# ERN_Main.net
KiCad netlist of a schematic drawn in Altium Designer
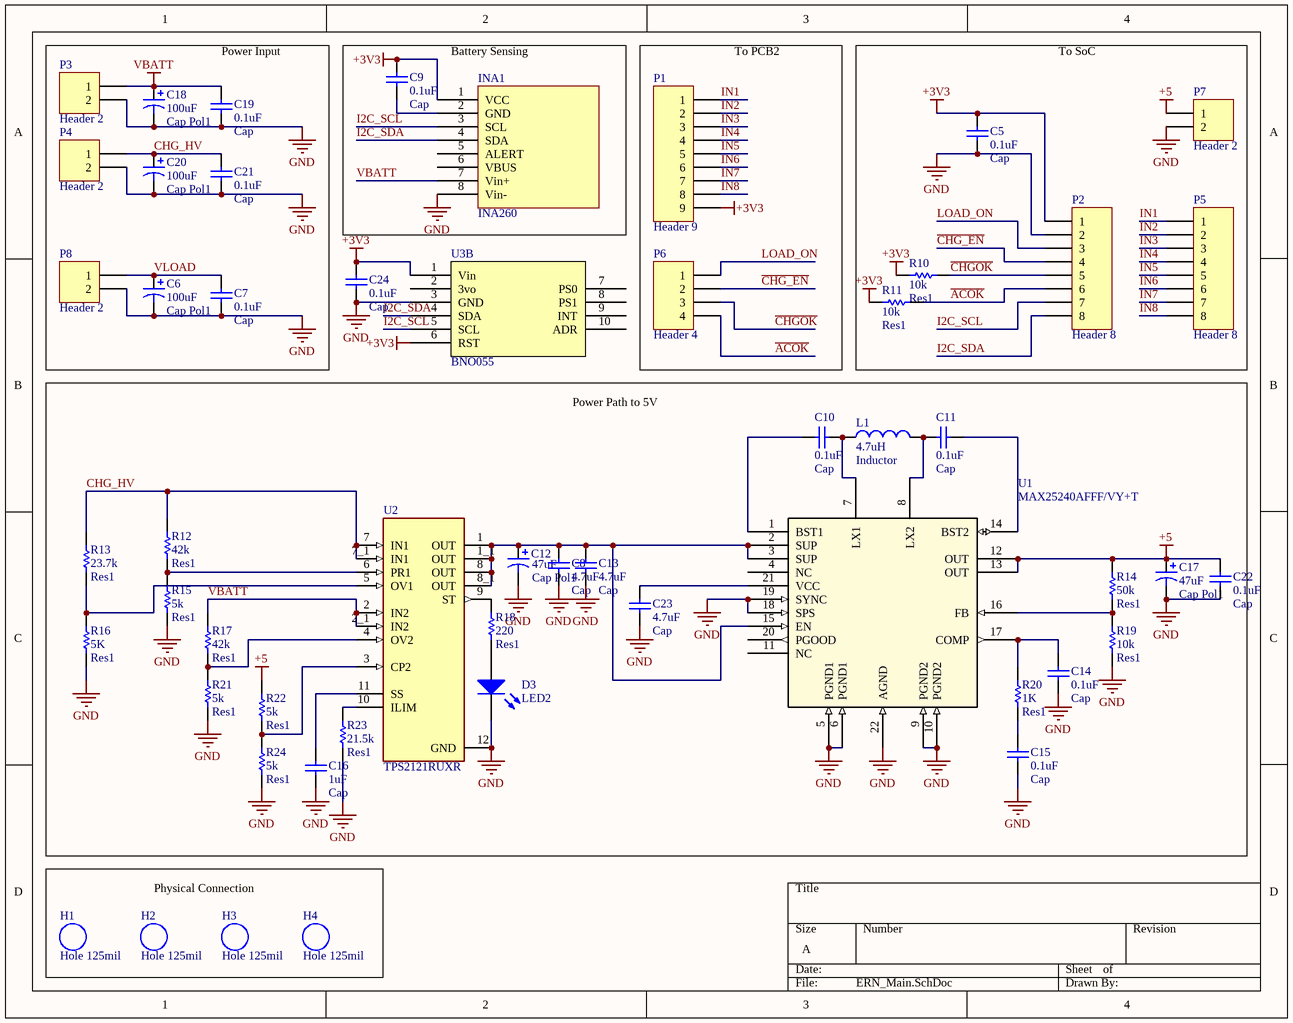
[diagram p0: ERN_Main.SchDoc]

(export (version "E")
  (design (tool "Eeschema 10.0.6"))
  (components
    (comp (ref "C5")
      (value "Cap")
      (footprint "RAD-0.3")
      (description "Capacitor")
      (fields (field (name "ALTIUM_VALUE") "0.1uF") (field (name "PUBLISHER") "Altium Limited"))
      (libsource (lib "Miscellaneous Devices") (part "Cap"))
    )
    (comp (ref "C6")
      (value "Cap Pol1")
      (footprint "Cap_47uF_100uF")
      (description "Polarized Capacitor (Radial)")
      (fields (field (name "ALTIUM_VALUE") "100uF") (field (name "PUBLISHER") "Altium Limited"))
      (libsource (lib "Miscellaneous Devices") (part "Cap Pol1"))
    )
    (comp (ref "C7")
      (value "Cap")
      (footprint "RAD-0.3")
      (description "Capacitor")
      (fields (field (name "ALTIUM_VALUE") "0.1uF") (field (name "PUBLISHER") "Altium Limited"))
      (libsource (lib "Miscellaneous Devices") (part "Cap"))
    )
    (comp (ref "C8")
      (value "Cap")
      (footprint "c0805")
      (description "Capacitor")
      (fields (field (name "ALTIUM_VALUE") "4.7uF") (field (name "PUBLISHER") "Altium Limited"))
      (libsource (lib "Miscellaneous Devices") (part "Cap"))
    )
    (comp (ref "C9")
      (value "Cap")
      (footprint "RAD-0.3")
      (description "Capacitor")
      (fields (field (name "ALTIUM_VALUE") "0.1uF") (field (name "PUBLISHER") "Altium Limited"))
      (libsource (lib "Miscellaneous Devices") (part "Cap"))
    )
    (comp (ref "C10")
      (value "Cap")
      (footprint "c0805")
      (description "Capacitor")
      (fields (field (name "ALTIUM_VALUE") "0.1uF") (field (name "PUBLISHER") "Altium Limited"))
      (libsource (lib "Miscellaneous Devices") (part "Cap"))
    )
    (comp (ref "C11")
      (value "Cap")
      (footprint "c0805")
      (description "Capacitor")
      (fields (field (name "ALTIUM_VALUE") "0.1uF") (field (name "PUBLISHER") "Altium Limited"))
      (libsource (lib "Miscellaneous Devices") (part "Cap"))
    )
    (comp (ref "C12")
      (value "Cap Pol1")
      (footprint "Cap_47uF_100uF")
      (description "Polarized Capacitor (Radial)")
      (fields (field (name "ALTIUM_VALUE") "47uF") (field (name "PUBLISHER") "Altium Limited"))
      (libsource (lib "Miscellaneous Devices") (part "Cap Pol1"))
    )
    (comp (ref "C13")
      (value "Cap")
      (footprint "c0805")
      (description "Capacitor")
      (fields (field (name "ALTIUM_VALUE") "4.7uF") (field (name "PUBLISHER") "Altium Limited"))
      (libsource (lib "Miscellaneous Devices") (part "Cap"))
    )
    (comp (ref "C14")
      (value "Cap")
      (footprint "RAD-0.3")
      (description "Capacitor")
      (fields (field (name "ALTIUM_VALUE") "0.1uF") (field (name "PUBLISHER") "Altium Limited"))
      (libsource (lib "Miscellaneous Devices") (part "Cap"))
    )
    (comp (ref "C15")
      (value "Cap")
      (footprint "RAD-0.3")
      (description "Capacitor")
      (fields (field (name "ALTIUM_VALUE") "0.1uF") (field (name "PUBLISHER") "Altium Limited"))
      (libsource (lib "Miscellaneous Devices") (part "Cap"))
    )
    (comp (ref "C16")
      (value "Cap")
      (footprint "C0805")
      (description "Capacitor")
      (fields (field (name "ALTIUM_VALUE") "1uF") (field (name "PUBLISHER") "Altium Limited"))
      (libsource (lib "Miscellaneous Devices") (part "Cap"))
    )
    (comp (ref "C17")
      (value "Cap Pol1")
      (footprint "Cap_47uF_100uF")
      (description "Polarized Capacitor (Radial)")
      (fields (field (name "ALTIUM_VALUE") "47uF") (field (name "PUBLISHER") "Altium Limited"))
      (libsource (lib "Miscellaneous Devices") (part "Cap Pol1"))
    )
    (comp (ref "C18")
      (value "Cap Pol1")
      (footprint "Cap_47uF_100uF")
      (description "Polarized Capacitor (Radial)")
      (fields (field (name "ALTIUM_VALUE") "100uF") (field (name "PUBLISHER") "Altium Limited"))
      (libsource (lib "Miscellaneous Devices") (part "Cap Pol1"))
    )
    (comp (ref "C19")
      (value "Cap")
      (footprint "RAD-0.3")
      (description "Capacitor")
      (fields (field (name "ALTIUM_VALUE") "0.1uF") (field (name "PUBLISHER") "Altium Limited"))
      (libsource (lib "Miscellaneous Devices") (part "Cap"))
    )
    (comp (ref "C20")
      (value "Cap Pol1")
      (footprint "Cap_47uF_100uF")
      (description "Polarized Capacitor (Radial)")
      (fields (field (name "ALTIUM_VALUE") "100uF") (field (name "PUBLISHER") "Altium Limited"))
      (libsource (lib "Miscellaneous Devices") (part "Cap Pol1"))
    )
    (comp (ref "C21")
      (value "Cap")
      (footprint "RAD-0.3")
      (description "Capacitor")
      (fields (field (name "ALTIUM_VALUE") "0.1uF") (field (name "PUBLISHER") "Altium Limited"))
      (libsource (lib "Miscellaneous Devices") (part "Cap"))
    )
    (comp (ref "C22")
      (value "Cap")
      (footprint "RAD-0.3")
      (description "Capacitor")
      (fields (field (name "ALTIUM_VALUE") "0.1uF") (field (name "PUBLISHER") "Altium Limited"))
      (libsource (lib "Miscellaneous Devices") (part "Cap"))
    )
    (comp (ref "C23")
      (value "Cap")
      (footprint "c0805")
      (description "Capacitor")
      (fields (field (name "ALTIUM_VALUE") "4.7uF") (field (name "PUBLISHER") "Altium Limited"))
      (libsource (lib "Miscellaneous Devices") (part "Cap"))
    )
    (comp (ref "C24")
      (value "Cap")
      (footprint "RAD-0.3")
      (description "Capacitor")
      (fields (field (name "ALTIUM_VALUE") "0.1uF") (field (name "PUBLISHER") "Altium Limited"))
      (libsource (lib "Miscellaneous Devices") (part "Cap"))
    )
    (comp (ref "D3")
      (value "LED2")
      (footprint "led-0")
      (description "Typical RED, GREEN, YELLOW, AMBER GaAs LED")
      (fields (field (name "PUBLISHER") "Altium Limited"))
      (libsource (lib "Miscellaneous Devices") (part "LED2"))
    )
    (comp (ref "H1")
      (value "Hole 125mil")
      (footprint "Hole 125mil")
      (libsource (lib "ECE Lib 22") (part "Hole 125mil"))
    )
    (comp (ref "H2")
      (value "Hole 125mil")
      (footprint "Hole 125mil")
      (libsource (lib "ECE Lib 22") (part "Hole 125mil"))
    )
    (comp (ref "H3")
      (value "Hole 125mil")
      (footprint "Hole 125mil")
      (libsource (lib "ECE Lib 22") (part "Hole 125mil"))
    )
    (comp (ref "H4")
      (value "Hole 125mil")
      (footprint "Hole 125mil")
      (libsource (lib "ECE Lib 22") (part "Hole 125mil"))
    )
    (comp (ref "INA1")
      (value "INA260")
      (footprint "INA260_Breakout")
      (description "Voltage and current sensor")
      (libsource (lib "ERN") (part "INA260_Breakout"))
    )
    (comp (ref "L1")
      (value "Inductor")
      (footprint "SRP6540-4R7M")
      (fields (field (name "ALTIUM_VALUE") "4.7uH") (field (name "PUBLISHER") "Altium Limited"))
      (libsource (lib "Miscellaneous Devices") (part "Inductor"))
    )
    (comp (ref "P1")
      (value "Header 9")
      (footprint "HDR1X9")
      (description "Header, 9-Pin")
      (fields (field (name "PUBLISHER") "Altium Limited"))
      (libsource (lib "Miscellaneous Connectors") (part "Header 9"))
    )
    (comp (ref "P2")
      (value "Header 8")
      (footprint "HDR1X8")
      (description "Header, 8-Pin")
      (fields (field (name "PUBLISHER") "Altium Limited"))
      (libsource (lib "Miscellaneous Connectors") (part "Header 8"))
    )
    (comp (ref "P3")
      (value "Header 2")
      (footprint "HDR1X2")
      (description "Header, 2-Pin")
      (fields (field (name "PUBLISHER") "Altium Limited"))
      (libsource (lib "Miscellaneous Connectors") (part "Header 2"))
    )
    (comp (ref "P4")
      (value "Header 2")
      (footprint "HDR1X2")
      (description "Header, 2-Pin")
      (fields (field (name "PUBLISHER") "Altium Limited"))
      (libsource (lib "Miscellaneous Connectors") (part "Header 2"))
    )
    (comp (ref "P5")
      (value "Header 8")
      (footprint "HDR1X8")
      (description "Header, 8-Pin")
      (fields (field (name "PUBLISHER") "Altium Limited"))
      (libsource (lib "Miscellaneous Connectors") (part "Header 8"))
    )
    (comp (ref "P6")
      (value "Header 4")
      (footprint "HDR1X4")
      (description "Header, 4-Pin")
      (fields (field (name "PUBLISHER") "Altium Limited"))
      (libsource (lib "Miscellaneous Connectors") (part "Header 4"))
    )
    (comp (ref "P7")
      (value "Header 2")
      (footprint "HDR1X2")
      (description "Header, 2-Pin")
      (fields (field (name "PUBLISHER") "Altium Limited"))
      (libsource (lib "") (part "Header 2_1"))
    )
    (comp (ref "P8")
      (value "Header 2")
      (footprint "HDR1X2")
      (description "Header, 2-Pin")
      (fields (field (name "PUBLISHER") "Altium Limited"))
      (libsource (lib "Miscellaneous Connectors") (part "Header 2"))
    )
    (comp (ref "R10")
      (value "Res1")
      (footprint "AXIAL-0.3")
      (description "Resistor")
      (fields (field (name "ALTIUM_VALUE") "10k") (field (name "PUBLISHER") "Altium Limited"))
      (libsource (lib "Miscellaneous Devices") (part "Res1"))
    )
    (comp (ref "R11")
      (value "Res1")
      (footprint "AXIAL-0.3")
      (description "Resistor")
      (fields (field (name "ALTIUM_VALUE") "10k") (field (name "PUBLISHER") "Altium Limited"))
      (libsource (lib "Miscellaneous Devices") (part "Res1"))
    )
    (comp (ref "R12")
      (value "Res1")
      (footprint "AXIAL-0.3")
      (description "Resistor")
      (fields (field (name "ALTIUM_VALUE") "42k") (field (name "PUBLISHER") "Altium Limited"))
      (libsource (lib "Miscellaneous Devices") (part "Res1"))
    )
    (comp (ref "R13")
      (value "Res1")
      (footprint "AXIAL-0.3")
      (description "Resistor")
      (fields (field (name "ALTIUM_VALUE") "23.7k") (field (name "PUBLISHER") "Altium Limited"))
      (libsource (lib "Miscellaneous Devices") (part "Res1"))
    )
    (comp (ref "R14")
      (value "Res1")
      (footprint "AXIAL-0.3")
      (description "Resistor")
      (fields (field (name "ALTIUM_VALUE") "50k") (field (name "PUBLISHER") "Altium Limited"))
      (libsource (lib "Miscellaneous Devices") (part "Res1"))
    )
    (comp (ref "R15")
      (value "Res1")
      (footprint "AXIAL-0.3")
      (description "Resistor")
      (fields (field (name "ALTIUM_VALUE") "5k") (field (name "PUBLISHER") "Altium Limited"))
      (libsource (lib "Miscellaneous Devices") (part "Res1"))
    )
    (comp (ref "R16")
      (value "Res1")
      (footprint "AXIAL-0.3")
      (description "Resistor")
      (fields (field (name "ALTIUM_VALUE") "5K") (field (name "PUBLISHER") "Altium Limited"))
      (libsource (lib "Miscellaneous Devices") (part "Res1"))
    )
    (comp (ref "R17")
      (value "Res1")
      (footprint "AXIAL-0.3")
      (description "Resistor")
      (fields (field (name "ALTIUM_VALUE") "42k") (field (name "PUBLISHER") "Altium Limited"))
      (libsource (lib "Miscellaneous Devices") (part "Res1"))
    )
    (comp (ref "R18")
      (value "Res1")
      (footprint "AXIAL-0.3")
      (description "Resistor")
      (fields (field (name "ALTIUM_VALUE") "220") (field (name "PUBLISHER") "Altium Limited"))
      (libsource (lib "Miscellaneous Devices") (part "Res1"))
    )
    (comp (ref "R19")
      (value "Res1")
      (footprint "AXIAL-0.3")
      (description "Resistor")
      (fields (field (name "ALTIUM_VALUE") "10k") (field (name "PUBLISHER") "Altium Limited"))
      (libsource (lib "Miscellaneous Devices") (part "Res1"))
    )
    (comp (ref "R20")
      (value "Res1")
      (footprint "AXIAL-0.3")
      (description "Resistor")
      (fields (field (name "ALTIUM_VALUE") "1K") (field (name "PUBLISHER") "Altium Limited"))
      (libsource (lib "Miscellaneous Devices") (part "Res1"))
    )
    (comp (ref "R21")
      (value "Res1")
      (footprint "AXIAL-0.3")
      (description "Resistor")
      (fields (field (name "ALTIUM_VALUE") "5k") (field (name "PUBLISHER") "Altium Limited"))
      (libsource (lib "Miscellaneous Devices") (part "Res1"))
    )
    (comp (ref "R22")
      (value "Res1")
      (footprint "AXIAL-0.3")
      (description "Resistor")
      (fields (field (name "ALTIUM_VALUE") "5k") (field (name "PUBLISHER") "Altium Limited"))
      (libsource (lib "Miscellaneous Devices") (part "Res1"))
    )
    (comp (ref "R23")
      (value "Res1")
      (footprint "AXIAL-0.3")
      (description "Resistor")
      (fields (field (name "ALTIUM_VALUE") "21.5k") (field (name "PUBLISHER") "Altium Limited"))
      (libsource (lib "Miscellaneous Devices") (part "Res1"))
    )
    (comp (ref "R24")
      (value "Res1")
      (footprint "AXIAL-0.3")
      (description "Resistor")
      (fields (field (name "ALTIUM_VALUE") "5k") (field (name "PUBLISHER") "Altium Limited"))
      (libsource (lib "Miscellaneous Devices") (part "Res1"))
    )
    (comp (ref "U1")
      (value "MAX25240AFFF/VY+T")
      (footprint "21-100399_90-100137_ADI - duplicate")
      (description "Automotive 2V to 36V, 6A Buck-Boost Converters")
      (fields (field (name "COPYRIGHT") "Copyright (C) 2025 Ultra Librarian. All rights reserved."))
      (libsource (lib "ERN") (part "MAX25240AFFFVY+T"))
    )
    (comp (ref "U2")
      (value "TPS2121RUXR")
      (footprint "IC_TPS2121RUXR")
      (description "2.7-V&nbsp;to 22-V, 56-mâ„¦, 4.5-A, power mux with seamless switchover")
      (fields (field (name "MF") "Texas Instruments"))
      (libsource (lib "ERN") (part "TPS2121RUXR"))
    )
    (comp (ref "U3")
      (value "BNO055")
      (footprint "BNO055_Breakout")
      (description "Adafruit IMU Breakout")
      (libsource (lib "ERN") (part "BNO055_Breakout"))
    )
  )
  (nets
    (net (code "1") (name "+3V3") (class "Default")
      (node (ref "C24") (pin "1") (pinfunction "1_1") (pintype "passive"))
      (node (ref "C5") (pin "2") (pinfunction "2_2") (pintype "passive"))
      (node (ref "C9") (pin "1") (pinfunction "1_1") (pintype "passive"))
      (node (ref "INA1") (pin "1") (pinfunction "VCC_1") (pintype "passive"))
      (node (ref "P1") (pin "9") (pinfunction "9_9") (pintype "passive"))
      (node (ref "P2") (pin "1") (pinfunction "1_1") (pintype "passive"))
      (node (ref "R10") (pin "1") (pinfunction "1_1") (pintype "passive"))
      (node (ref "R11") (pin "1") (pinfunction "1_1") (pintype "passive"))
      (node (ref "U3") (pin "1") (pinfunction "Vin_1") (pintype "passive"))
      (node (ref "U3") (pin "6") (pinfunction "RST_6") (pintype "passive"))
    )
    (net (code "2") (name "+5") (class "Default")
      (node (ref "C17") (pin "1") (pinfunction "1_1") (pintype "passive"))
      (node (ref "C22") (pin "2") (pinfunction "2_2") (pintype "passive"))
      (node (ref "P7") (pin "1") (pinfunction "1_1") (pintype "passive"))
      (node (ref "R14") (pin "1") (pinfunction "1_1") (pintype "passive"))
      (node (ref "R22") (pin "1") (pinfunction "1_1") (pintype "passive"))
      (node (ref "U1") (pin "12") (pinfunction "OUT_12") (pintype "power_in"))
      (node (ref "U1") (pin "13") (pinfunction "OUT_13") (pintype "power_in"))
    )
    (net (code "3") (name "/CHG_HV") (class "Default")
      (node (ref "C20") (pin "1") (pinfunction "1_1") (pintype "passive"))
      (node (ref "C21") (pin "2") (pinfunction "2_2") (pintype "passive"))
      (node (ref "P4") (pin "1") (pinfunction "1_1") (pintype "passive"))
      (node (ref "R12") (pin "1") (pinfunction "1_1") (pintype "passive"))
      (node (ref "R13") (pin "1") (pinfunction "1_1") (pintype "passive"))
      (node (ref "U2") (pin "7") (pinfunction "IN1_7") (pintype "input"))
      (node (ref "U2") (pin "7_1") (pinfunction "IN1_7_1") (pintype "input"))
    )
    (net (code "4") (name "/I2C_SCL") (class "Default")
      (node (ref "INA1") (pin "3") (pinfunction "SCL_3") (pintype "passive"))
      (node (ref "P2") (pin "7") (pinfunction "7_7") (pintype "passive"))
      (node (ref "U3") (pin "5") (pinfunction "SCL_5") (pintype "passive"))
    )
    (net (code "5") (name "/I2C_SDA") (class "Default")
      (node (ref "INA1") (pin "4") (pinfunction "SDA_4") (pintype "passive"))
      (node (ref "P2") (pin "8") (pinfunction "8_8") (pintype "passive"))
      (node (ref "U3") (pin "4") (pinfunction "SDA_4") (pintype "passive"))
    )
    (net (code "6") (name "/IN1") (class "Default")
      (node (ref "P1") (pin "1") (pinfunction "1_1") (pintype "passive"))
      (node (ref "P5") (pin "1") (pinfunction "1_1") (pintype "passive"))
    )
    (net (code "7") (name "/IN2") (class "Default")
      (node (ref "P1") (pin "2") (pinfunction "2_2") (pintype "passive"))
      (node (ref "P5") (pin "2") (pinfunction "2_2") (pintype "passive"))
    )
    (net (code "8") (name "/IN3") (class "Default")
      (node (ref "P1") (pin "3") (pinfunction "3_3") (pintype "passive"))
      (node (ref "P5") (pin "3") (pinfunction "3_3") (pintype "passive"))
    )
    (net (code "9") (name "/IN4") (class "Default")
      (node (ref "P1") (pin "4") (pinfunction "4_4") (pintype "passive"))
      (node (ref "P5") (pin "4") (pinfunction "4_4") (pintype "passive"))
    )
    (net (code "10") (name "/IN5") (class "Default")
      (node (ref "P1") (pin "5") (pinfunction "5_5") (pintype "passive"))
      (node (ref "P5") (pin "5") (pinfunction "5_5") (pintype "passive"))
    )
    (net (code "11") (name "/IN6") (class "Default")
      (node (ref "P1") (pin "6") (pinfunction "6_6") (pintype "passive"))
      (node (ref "P5") (pin "6") (pinfunction "6_6") (pintype "passive"))
    )
    (net (code "12") (name "/IN7") (class "Default")
      (node (ref "P1") (pin "7") (pinfunction "7_7") (pintype "passive"))
      (node (ref "P5") (pin "7") (pinfunction "7_7") (pintype "passive"))
    )
    (net (code "13") (name "/IN8") (class "Default")
      (node (ref "P1") (pin "8") (pinfunction "8_8") (pintype "passive"))
      (node (ref "P5") (pin "8") (pinfunction "8_8") (pintype "passive"))
    )
    (net (code "14") (name "/LOAD_ON") (class "Default")
      (node (ref "P2") (pin "3") (pinfunction "3_3") (pintype "passive"))
      (node (ref "P6") (pin "1") (pinfunction "1_1") (pintype "passive"))
    )
    (net (code "15") (name "/VLOAD") (class "Default")
      (node (ref "C6") (pin "1") (pinfunction "1_1") (pintype "passive"))
      (node (ref "C7") (pin "2") (pinfunction "2_2") (pintype "passive"))
      (node (ref "P8") (pin "1") (pinfunction "1_1") (pintype "passive"))
    )
    (net (code "16") (name "/~{ACOK}") (class "Default")
      (node (ref "P2") (pin "6") (pinfunction "6_6") (pintype "passive"))
      (node (ref "P6") (pin "4") (pinfunction "4_4") (pintype "passive"))
      (node (ref "R11") (pin "2") (pinfunction "2_2") (pintype "passive"))
    )
    (net (code "17") (name "/~{CHGOK}") (class "Default")
      (node (ref "P2") (pin "5") (pinfunction "5_5") (pintype "passive"))
      (node (ref "P6") (pin "3") (pinfunction "3_3") (pintype "passive"))
      (node (ref "R10") (pin "2") (pinfunction "2_2") (pintype "passive"))
    )
    (net (code "18") (name "/~{CHG_EN}") (class "Default")
      (node (ref "P2") (pin "4") (pinfunction "4_4") (pintype "passive"))
      (node (ref "P6") (pin "2") (pinfunction "2_2") (pintype "passive"))
    )
    (net (code "19") (name "GND") (class "Default")
      (node (ref "C12") (pin "2") (pinfunction "2_2") (pintype "passive"))
      (node (ref "C13") (pin "1") (pinfunction "1_1") (pintype "passive"))
      (node (ref "C14") (pin "1") (pinfunction "1_1") (pintype "passive"))
      (node (ref "C15") (pin "1") (pinfunction "1_1") (pintype "passive"))
      (node (ref "C16") (pin "2") (pinfunction "2_2") (pintype "passive"))
      (node (ref "C17") (pin "2") (pinfunction "2_2") (pintype "passive"))
      (node (ref "C18") (pin "2") (pinfunction "2_2") (pintype "passive"))
      (node (ref "C19") (pin "1") (pinfunction "1_1") (pintype "passive"))
      (node (ref "C20") (pin "2") (pinfunction "2_2") (pintype "passive"))
      (node (ref "C21") (pin "1") (pinfunction "1_1") (pintype "passive"))
      (node (ref "C22") (pin "1") (pinfunction "1_1") (pintype "passive"))
      (node (ref "C23") (pin "1") (pinfunction "1_1") (pintype "passive"))
      (node (ref "C24") (pin "2") (pinfunction "2_2") (pintype "passive"))
      (node (ref "C5") (pin "1") (pinfunction "1_1") (pintype "passive"))
      (node (ref "C6") (pin "2") (pinfunction "2_2") (pintype "passive"))
      (node (ref "C7") (pin "1") (pinfunction "1_1") (pintype "passive"))
      (node (ref "C8") (pin "1") (pinfunction "1_1") (pintype "passive"))
      (node (ref "D3") (pin "2") (pinfunction "K_2") (pintype "passive"))
      (node (ref "INA1") (pin "8") (pinfunction "Vin-_8") (pintype "passive"))
      (node (ref "P2") (pin "2") (pinfunction "2_2") (pintype "passive"))
      (node (ref "P3") (pin "2") (pinfunction "2_2") (pintype "passive"))
      (node (ref "P4") (pin "2") (pinfunction "2_2") (pintype "passive"))
      (node (ref "P7") (pin "2") (pinfunction "2_2") (pintype "passive"))
      (node (ref "P8") (pin "2") (pinfunction "2_2") (pintype "passive"))
      (node (ref "R15") (pin "2") (pinfunction "2_2") (pintype "passive"))
      (node (ref "R16") (pin "2") (pinfunction "2_2") (pintype "passive"))
      (node (ref "R19") (pin "2") (pinfunction "2_2") (pintype "passive"))
      (node (ref "R21") (pin "2") (pinfunction "2_2") (pintype "passive"))
      (node (ref "R23") (pin "2") (pinfunction "2_2") (pintype "passive"))
      (node (ref "R24") (pin "2") (pinfunction "2_2") (pintype "passive"))
      (node (ref "U1") (pin "10") (pinfunction "PGND2_10") (pintype "input"))
      (node (ref "U1") (pin "18") (pinfunction "SPS_18") (pintype "input"))
      (node (ref "U1") (pin "19") (pinfunction "SYNC_19") (pintype "input"))
      (node (ref "U1") (pin "22") (pinfunction "AGND_22") (pintype "input"))
      (node (ref "U1") (pin "5") (pinfunction "PGND1_5") (pintype "input"))
      (node (ref "U1") (pin "6") (pinfunction "PGND1_6") (pintype "input"))
      (node (ref "U1") (pin "9") (pinfunction "PGND2_9") (pintype "input"))
      (node (ref "U2") (pin "12") (pinfunction "GND_12") (pintype "power_in"))
      (node (ref "U3") (pin "3") (pinfunction "GND_3") (pintype "passive"))
    )
    (net (code "20") (name "Net-(C15-Pad2)") (class "Default")
      (node (ref "C15") (pin "2") (pinfunction "2_2") (pintype "passive"))
      (node (ref "R20") (pin "2") (pinfunction "2_2") (pintype "passive"))
    )
    (net (code "21") (name "Net-(D3-A)") (class "Default")
      (node (ref "D3") (pin "1") (pinfunction "A_1") (pintype "passive"))
      (node (ref "R18") (pin "2") (pinfunction "2_2") (pintype "passive"))
    )
    (net (code "22") (name "Net-(INA1-GND)") (class "Default")
      (node (ref "C9") (pin "2") (pinfunction "2_2") (pintype "passive"))
      (node (ref "INA1") (pin "2") (pinfunction "GND_2") (pintype "passive"))
    )
    (net (code "23") (name "Net-(U1-BST1)") (class "Default")
      (node (ref "C10") (pin "1") (pinfunction "1_1") (pintype "passive"))
      (node (ref "U1") (pin "1") (pinfunction "BST1_1") (pintype "power_in"))
    )
    (net (code "24") (name "Net-(U1-BST2)") (class "Default")
      (node (ref "C11") (pin "2") (pinfunction "2_2") (pintype "passive"))
      (node (ref "U1") (pin "14") (pinfunction "BST2_14") (pintype "bidirectional"))
    )
    (net (code "25") (name "Net-(U1-COMP)") (class "Default")
      (node (ref "C14") (pin "2") (pinfunction "2_2") (pintype "passive"))
      (node (ref "R20") (pin "1") (pinfunction "1_1") (pintype "passive"))
      (node (ref "U1") (pin "17") (pinfunction "COMP_17") (pintype "output"))
    )
    (net (code "26") (name "Net-(U1-EN)") (class "Default")
      (node (ref "C12") (pin "1") (pinfunction "1_1") (pintype "passive"))
      (node (ref "C13") (pin "2") (pinfunction "2_2") (pintype "passive"))
      (node (ref "C8") (pin "2") (pinfunction "2_2") (pintype "passive"))
      (node (ref "U1") (pin "15") (pinfunction "EN_15") (pintype "input"))
      (node (ref "U1") (pin "2") (pinfunction "SUP_2") (pintype "power_in"))
      (node (ref "U1") (pin "3") (pinfunction "SUP_3") (pintype "power_in"))
      (node (ref "U2") (pin "1") (pinfunction "OUT_1") (pintype "power_in"))
      (node (ref "U2") (pin "1_1") (pinfunction "OUT_1_1") (pintype "power_in"))
      (node (ref "U2") (pin "8") (pinfunction "OUT_8") (pintype "power_in"))
      (node (ref "U2") (pin "8_1") (pinfunction "OUT_8_1") (pintype "power_in"))
    )
    (net (code "27") (name "Net-(U1-FB)") (class "Default")
      (node (ref "R14") (pin "2") (pinfunction "2_2") (pintype "passive"))
      (node (ref "R19") (pin "1") (pinfunction "1_1") (pintype "passive"))
      (node (ref "U1") (pin "16") (pinfunction "FB_16") (pintype "input"))
    )
    (net (code "28") (name "Net-(U1-LX1)") (class "Default")
      (node (ref "C10") (pin "2") (pinfunction "2_2") (pintype "passive"))
      (node (ref "L1") (pin "1") (pinfunction "1_1") (pintype "passive"))
      (node (ref "U1") (pin "7") (pinfunction "LX1_7") (pintype "power_in"))
    )
    (net (code "29") (name "Net-(U1-LX2)") (class "Default")
      (node (ref "C11") (pin "1") (pinfunction "1_1") (pintype "passive"))
      (node (ref "L1") (pin "2") (pinfunction "2_2") (pintype "passive"))
      (node (ref "U1") (pin "8") (pinfunction "LX2_8") (pintype "power_in"))
    )
    (net (code "30") (name "Net-(U1-VCC)") (class "Default")
      (node (ref "C23") (pin "2") (pinfunction "2_2") (pintype "passive"))
      (node (ref "U1") (pin "21") (pinfunction "VCC_21") (pintype "power_in"))
    )
    (net (code "31") (name "Net-(U2-CP2)") (class "Default")
      (node (ref "R22") (pin "2") (pinfunction "2_2") (pintype "passive"))
      (node (ref "R24") (pin "1") (pinfunction "1_1") (pintype "passive"))
      (node (ref "U2") (pin "3") (pinfunction "CP2_3") (pintype "input"))
    )
    (net (code "32") (name "Net-(U2-ILIM)") (class "Default")
      (node (ref "R23") (pin "1") (pinfunction "1_1") (pintype "passive"))
      (node (ref "U2") (pin "10") (pinfunction "ILIM_10") (pintype "passive"))
    )
    (net (code "33") (name "Net-(U2-OV1)") (class "Default")
      (node (ref "R13") (pin "2") (pinfunction "2_2") (pintype "passive"))
      (node (ref "R16") (pin "1") (pinfunction "1_1") (pintype "passive"))
      (node (ref "U2") (pin "5") (pinfunction "OV1_5") (pintype "input"))
    )
    (net (code "34") (name "Net-(U2-OV2)") (class "Default")
      (node (ref "R17") (pin "2") (pinfunction "2_2") (pintype "passive"))
      (node (ref "R21") (pin "1") (pinfunction "1_1") (pintype "passive"))
      (node (ref "U2") (pin "4") (pinfunction "OV2_4") (pintype "input"))
    )
    (net (code "35") (name "Net-(U2-PR1)") (class "Default")
      (node (ref "R12") (pin "2") (pinfunction "2_2") (pintype "passive"))
      (node (ref "R15") (pin "1") (pinfunction "1_1") (pintype "passive"))
      (node (ref "U2") (pin "6") (pinfunction "PR1_6") (pintype "input"))
    )
    (net (code "36") (name "Net-(U2-SS)") (class "Default")
      (node (ref "C16") (pin "1") (pinfunction "1_1") (pintype "passive"))
      (node (ref "U2") (pin "11") (pinfunction "SS_11") (pintype "passive"))
    )
    (net (code "37") (name "Net-(U2-ST)") (class "Default")
      (node (ref "R18") (pin "1") (pinfunction "1_1") (pintype "passive"))
      (node (ref "U2") (pin "9") (pinfunction "ST_9") (pintype "output"))
    )
    (net (code "38") (name "VBATT") (class "Default")
      (node (ref "C18") (pin "1") (pinfunction "1_1") (pintype "passive"))
      (node (ref "C19") (pin "2") (pinfunction "2_2") (pintype "passive"))
      (node (ref "INA1") (pin "7") (pinfunction "Vin+_7") (pintype "passive"))
      (node (ref "P3") (pin "1") (pinfunction "1_1") (pintype "passive"))
      (node (ref "R17") (pin "1") (pinfunction "1_1") (pintype "passive"))
      (node (ref "U2") (pin "2") (pinfunction "IN2_2") (pintype "input"))
      (node (ref "U2") (pin "2_1") (pinfunction "IN2_2_1") (pintype "input"))
    )
    (net (code "39") (name "unconnected-(INA1-ALERT-Pad5)") (class "Default")
      (node (ref "INA1") (pin "5") (pinfunction "ALERT_5") (pintype "passive"))
    )
    (net (code "40") (name "unconnected-(INA1-VBUS-Pad6)") (class "Default")
      (node (ref "INA1") (pin "6") (pinfunction "VBUS_6") (pintype "passive"))
    )
    (net (code "41") (name "unconnected-(U1-NC-Pad4)") (class "Default")
      (node (ref "U1") (pin "4") (pinfunction "NC_4") (pintype "passive"))
    )
    (net (code "42") (name "unconnected-(U1-NC-Pad11)") (class "Default")
      (node (ref "U1") (pin "11") (pinfunction "NC_11") (pintype "passive"))
    )
    (net (code "43") (name "unconnected-(U1-PGOOD-Pad20)") (class "Default")
      (node (ref "U1") (pin "20") (pinfunction "PGOOD_20") (pintype "output"))
    )
    (net (code "44") (name "unconnected-(U3B-3vo-Pad2)") (class "Default")
      (node (ref "U3") (pin "2") (pinfunction "3vo_2") (pintype "passive"))
    )
    (net (code "45") (name "unconnected-(U3B-ADR-Pad10)") (class "Default")
      (node (ref "U3") (pin "10") (pinfunction "ADR_10") (pintype "passive"))
    )
    (net (code "46") (name "unconnected-(U3B-INT-Pad9)") (class "Default")
      (node (ref "U3") (pin "9") (pinfunction "INT_9") (pintype "passive"))
    )
    (net (code "47") (name "unconnected-(U3B-PS0-Pad7)") (class "Default")
      (node (ref "U3") (pin "7") (pinfunction "PS0_7") (pintype "passive"))
    )
    (net (code "48") (name "unconnected-(U3B-PS1-Pad8)") (class "Default")
      (node (ref "U3") (pin "8") (pinfunction "PS1_8") (pintype "passive"))
    )
  )
)
